# swiatlo.net
KiCad netlist of a schematic drawn in EAGLE
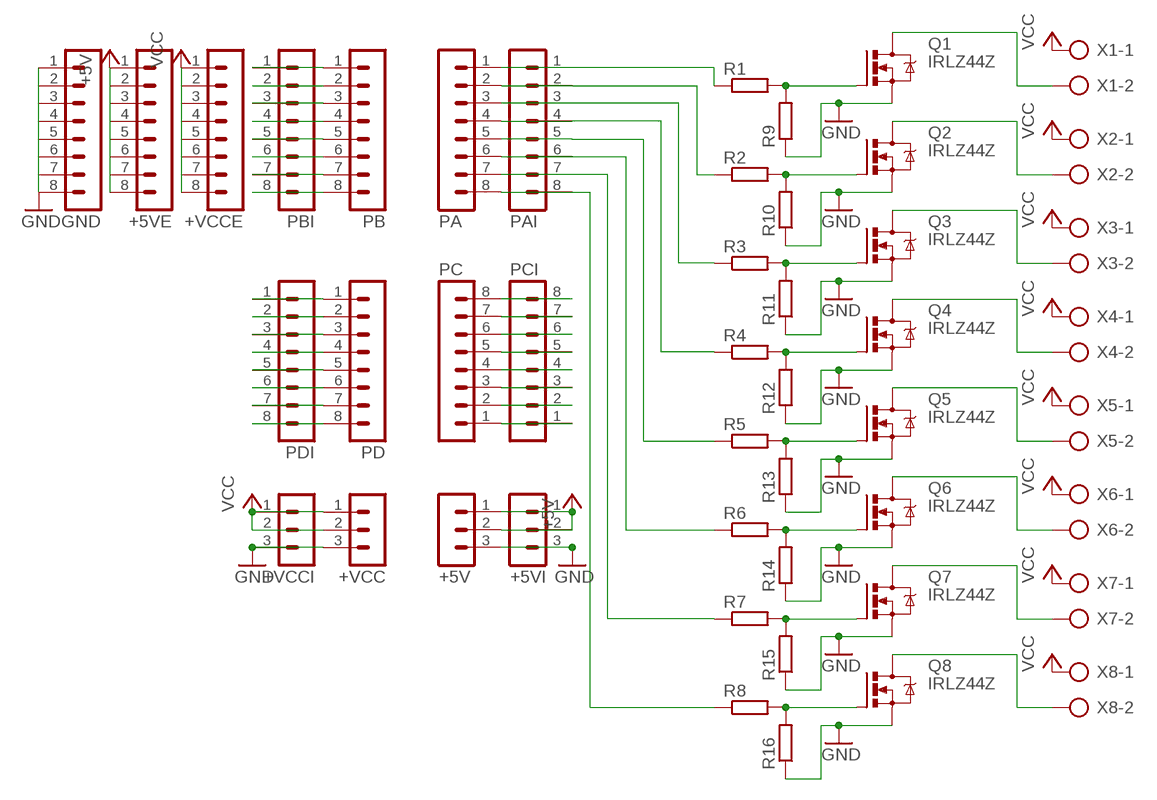
[diagram p0: schematic, sheet 1]

(export (version "E")
  (design (tool "Eeschema 10.0.6"))
  (components
    (comp (ref "+5V")
      (value "MA03-1")
      (footprint "eagle-import:MA03-1")
      (libsource (lib "eagle-import") (part "MA03-1"))
    )
    (comp (ref "+5VE")
      (value "MA08-1")
      (footprint "eagle-import:MA08-1")
      (libsource (lib "eagle-import") (part "MA08-1"))
    )
    (comp (ref "+5VI")
      (value "MA03-1")
      (footprint "eagle-import:MA03-1")
      (libsource (lib "eagle-import") (part "MA03-1"))
    )
    (comp (ref "+VCC")
      (value "MA03-1")
      (footprint "eagle-import:MA03-1")
      (libsource (lib "eagle-import") (part "MA03-1"))
    )
    (comp (ref "+VCCE")
      (value "MA08-1")
      (footprint "eagle-import:MA08-1")
      (libsource (lib "eagle-import") (part "MA08-1"))
    )
    (comp (ref "+VCCI")
      (value "MA03-1")
      (footprint "eagle-import:MA03-1")
      (libsource (lib "eagle-import") (part "MA03-1"))
    )
    (comp (ref "GND")
      (value "MA08-1")
      (footprint "eagle-import:MA08-1")
      (libsource (lib "eagle-import") (part "MA08-1"))
    )
    (comp (ref "PA")
      (value "MA08-1")
      (footprint "eagle-import:MA08-1")
      (libsource (lib "eagle-import") (part "MA08-1"))
    )
    (comp (ref "PAI")
      (value "MA08-1")
      (footprint "eagle-import:MA08-1")
      (libsource (lib "eagle-import") (part "MA08-1"))
    )
    (comp (ref "PB")
      (value "MA08-1")
      (footprint "eagle-import:MA08-1")
      (libsource (lib "eagle-import") (part "MA08-1"))
    )
    (comp (ref "PBI")
      (value "MA08-1")
      (footprint "eagle-import:MA08-1")
      (libsource (lib "eagle-import") (part "MA08-1"))
    )
    (comp (ref "PC")
      (value "MA08-1")
      (footprint "eagle-import:MA08-1")
      (libsource (lib "eagle-import") (part "MA08-1"))
    )
    (comp (ref "PCI")
      (value "MA08-1")
      (footprint "eagle-import:MA08-1")
      (libsource (lib "eagle-import") (part "MA08-1"))
    )
    (comp (ref "PD")
      (value "MA08-1")
      (footprint "eagle-import:MA08-1")
      (libsource (lib "eagle-import") (part "MA08-1"))
    )
    (comp (ref "PDI")
      (value "MA08-1")
      (footprint "eagle-import:MA08-1")
      (libsource (lib "eagle-import") (part "MA08-1"))
    )
    (comp (ref "Q1")
      (value "IRLZ44Z")
      (footprint "eagle-import:TO220BH")
      (libsource (lib "eagle-import") (part "IRLZ44Z"))
    )
    (comp (ref "Q2")
      (value "IRLZ44Z")
      (footprint "eagle-import:TO220BH")
      (libsource (lib "eagle-import") (part "IRLZ44Z"))
    )
    (comp (ref "Q3")
      (value "IRLZ44Z")
      (footprint "eagle-import:TO220BH")
      (libsource (lib "eagle-import") (part "IRLZ44Z"))
    )
    (comp (ref "Q4")
      (value "IRLZ44Z")
      (footprint "eagle-import:TO220BH")
      (libsource (lib "eagle-import") (part "IRLZ44Z"))
    )
    (comp (ref "Q5")
      (value "IRLZ44Z")
      (footprint "eagle-import:TO220BH")
      (libsource (lib "eagle-import") (part "IRLZ44Z"))
    )
    (comp (ref "Q6")
      (value "IRLZ44Z")
      (footprint "eagle-import:TO220BH")
      (libsource (lib "eagle-import") (part "IRLZ44Z"))
    )
    (comp (ref "Q7")
      (value "IRLZ44Z")
      (footprint "eagle-import:TO220BH")
      (libsource (lib "eagle-import") (part "IRLZ44Z"))
    )
    (comp (ref "Q8")
      (value "IRLZ44Z")
      (footprint "eagle-import:TO220BH")
      (libsource (lib "eagle-import") (part "IRLZ44Z"))
    )
    (comp (ref "R1")
      (value "R-EU_0204/7")
      (footprint "eagle-import:0204_7")
      (libsource (lib "eagle-import") (part "R-EU_0204/7"))
    )
    (comp (ref "R2")
      (value "R-EU_0204/7")
      (footprint "eagle-import:0204_7")
      (libsource (lib "eagle-import") (part "R-EU_0204/7"))
    )
    (comp (ref "R3")
      (value "R-EU_0204/7")
      (footprint "eagle-import:0204_7")
      (libsource (lib "eagle-import") (part "R-EU_0204/7"))
    )
    (comp (ref "R4")
      (value "R-EU_0204/7")
      (footprint "eagle-import:0204_7")
      (libsource (lib "eagle-import") (part "R-EU_0204/7"))
    )
    (comp (ref "R5")
      (value "R-EU_0204/7")
      (footprint "eagle-import:0204_7")
      (libsource (lib "eagle-import") (part "R-EU_0204/7"))
    )
    (comp (ref "R6")
      (value "R-EU_0204/7")
      (footprint "eagle-import:0204_7")
      (libsource (lib "eagle-import") (part "R-EU_0204/7"))
    )
    (comp (ref "R7")
      (value "R-EU_0204/7")
      (footprint "eagle-import:0204_7")
      (libsource (lib "eagle-import") (part "R-EU_0204/7"))
    )
    (comp (ref "R8")
      (value "R-EU_0204/7")
      (footprint "eagle-import:0204_7")
      (libsource (lib "eagle-import") (part "R-EU_0204/7"))
    )
    (comp (ref "R9")
      (value "R-EU_0204/7")
      (footprint "eagle-import:0204_7")
      (libsource (lib "eagle-import") (part "R-EU_0204/7"))
    )
    (comp (ref "R10")
      (value "R-EU_0204/7")
      (footprint "eagle-import:0204_7")
      (libsource (lib "eagle-import") (part "R-EU_0204/7"))
    )
    (comp (ref "R11")
      (value "R-EU_0204/7")
      (footprint "eagle-import:0204_7")
      (libsource (lib "eagle-import") (part "R-EU_0204/7"))
    )
    (comp (ref "R12")
      (value "R-EU_0204/7")
      (footprint "eagle-import:0204_7")
      (libsource (lib "eagle-import") (part "R-EU_0204/7"))
    )
    (comp (ref "R13")
      (value "R-EU_0204/7")
      (footprint "eagle-import:0204_7")
      (libsource (lib "eagle-import") (part "R-EU_0204/7"))
    )
    (comp (ref "R14")
      (value "R-EU_0204/7")
      (footprint "eagle-import:0204_7")
      (libsource (lib "eagle-import") (part "R-EU_0204/7"))
    )
    (comp (ref "R15")
      (value "R-EU_0204/7")
      (footprint "eagle-import:0204_7")
      (libsource (lib "eagle-import") (part "R-EU_0204/7"))
    )
    (comp (ref "R16")
      (value "R-EU_0204/7")
      (footprint "eagle-import:0204_7")
      (libsource (lib "eagle-import") (part "R-EU_0204/7"))
    )
    (comp (ref "X1")
      (value "AK300/2")
      (footprint "eagle-import:AK300_2")
      (libsource (lib "eagle-import") (part "AK300/2"))
    )
    (comp (ref "X2")
      (value "AK300/2")
      (footprint "eagle-import:AK300_2")
      (libsource (lib "eagle-import") (part "AK300/2"))
    )
    (comp (ref "X3")
      (value "AK300/2")
      (footprint "eagle-import:AK300_2")
      (libsource (lib "eagle-import") (part "AK300/2"))
    )
    (comp (ref "X4")
      (value "AK300/2")
      (footprint "eagle-import:AK300_2")
      (libsource (lib "eagle-import") (part "AK300/2"))
    )
    (comp (ref "X5")
      (value "AK300/2")
      (footprint "eagle-import:AK300_2")
      (libsource (lib "eagle-import") (part "AK300/2"))
    )
    (comp (ref "X6")
      (value "AK300/2")
      (footprint "eagle-import:AK300_2")
      (libsource (lib "eagle-import") (part "AK300/2"))
    )
    (comp (ref "X7")
      (value "AK300/2")
      (footprint "eagle-import:AK300_2")
      (libsource (lib "eagle-import") (part "AK300/2"))
    )
    (comp (ref "X8")
      (value "AK300/2")
      (footprint "eagle-import:AK300_2")
      (libsource (lib "eagle-import") (part "AK300/2"))
    )
  )
  (nets
    (net (code "1") (name "+5V") (class "Default")
      (node (ref "+5V") (pin "1") (pinfunction "1_1") (pintype "passive"))
      (node (ref "+5V") (pin "2") (pinfunction "2_2") (pintype "passive"))
      (node (ref "+5VE") (pin "1") (pinfunction "1_1") (pintype "passive"))
      (node (ref "+5VE") (pin "2") (pinfunction "2_2") (pintype "passive"))
      (node (ref "+5VE") (pin "3") (pinfunction "3_3") (pintype "passive"))
      (node (ref "+5VE") (pin "4") (pinfunction "4_4") (pintype "passive"))
      (node (ref "+5VE") (pin "5") (pinfunction "5_5") (pintype "passive"))
      (node (ref "+5VE") (pin "6") (pinfunction "6_6") (pintype "passive"))
      (node (ref "+5VE") (pin "7") (pinfunction "7_7") (pintype "passive"))
      (node (ref "+5VE") (pin "8") (pinfunction "8_8") (pintype "passive"))
      (node (ref "+5VI") (pin "1") (pinfunction "1_1") (pintype "passive"))
      (node (ref "+5VI") (pin "2") (pinfunction "2_2") (pintype "passive"))
    )
    (net (code "2") (name "GND") (class "Default")
      (node (ref "+5V") (pin "3") (pinfunction "3_3") (pintype "passive"))
      (node (ref "+5VI") (pin "3") (pinfunction "3_3") (pintype "passive"))
      (node (ref "+VCC") (pin "3") (pinfunction "3_3") (pintype "passive"))
      (node (ref "+VCCI") (pin "3") (pinfunction "3_3") (pintype "passive"))
      (node (ref "GND") (pin "1") (pinfunction "1_1") (pintype "passive"))
      (node (ref "GND") (pin "2") (pinfunction "2_2") (pintype "passive"))
      (node (ref "GND") (pin "3") (pinfunction "3_3") (pintype "passive"))
      (node (ref "GND") (pin "4") (pinfunction "4_4") (pintype "passive"))
      (node (ref "GND") (pin "5") (pinfunction "5_5") (pintype "passive"))
      (node (ref "GND") (pin "6") (pinfunction "6_6") (pintype "passive"))
      (node (ref "GND") (pin "7") (pinfunction "7_7") (pintype "passive"))
      (node (ref "GND") (pin "8") (pinfunction "8_8") (pintype "passive"))
      (node (ref "Q1") (pin "S") (pinfunction "S_S") (pintype "passive"))
      (node (ref "Q2") (pin "S") (pinfunction "S_S") (pintype "passive"))
      (node (ref "Q3") (pin "S") (pinfunction "S_S") (pintype "passive"))
      (node (ref "Q4") (pin "S") (pinfunction "S_S") (pintype "passive"))
      (node (ref "Q5") (pin "S") (pinfunction "S_S") (pintype "passive"))
      (node (ref "Q6") (pin "S") (pinfunction "S_S") (pintype "passive"))
      (node (ref "Q7") (pin "S") (pinfunction "S_S") (pintype "passive"))
      (node (ref "Q8") (pin "S") (pinfunction "S_S") (pintype "passive"))
      (node (ref "R10") (pin "1") (pinfunction "1_1") (pintype "passive"))
      (node (ref "R11") (pin "1") (pinfunction "1_1") (pintype "passive"))
      (node (ref "R12") (pin "1") (pinfunction "1_1") (pintype "passive"))
      (node (ref "R13") (pin "1") (pinfunction "1_1") (pintype "passive"))
      (node (ref "R14") (pin "1") (pinfunction "1_1") (pintype "passive"))
      (node (ref "R15") (pin "1") (pinfunction "1_1") (pintype "passive"))
      (node (ref "R16") (pin "1") (pinfunction "1_1") (pintype "passive"))
      (node (ref "R9") (pin "1") (pinfunction "1_1") (pintype "passive"))
    )
    (net (code "3") (name "Net-(PA-Pad1)") (class "Default")
      (node (ref "PA") (pin "1") (pinfunction "1_1") (pintype "passive"))
      (node (ref "PAI") (pin "1") (pinfunction "1_1") (pintype "passive"))
      (node (ref "R1") (pin "1") (pinfunction "1_1") (pintype "passive"))
    )
    (net (code "4") (name "Net-(PA-Pad2)") (class "Default")
      (node (ref "PA") (pin "2") (pinfunction "2_2") (pintype "passive"))
      (node (ref "PAI") (pin "2") (pinfunction "2_2") (pintype "passive"))
      (node (ref "R2") (pin "1") (pinfunction "1_1") (pintype "passive"))
    )
    (net (code "5") (name "Net-(PA-Pad3)") (class "Default")
      (node (ref "PA") (pin "3") (pinfunction "3_3") (pintype "passive"))
      (node (ref "PAI") (pin "3") (pinfunction "3_3") (pintype "passive"))
      (node (ref "R3") (pin "1") (pinfunction "1_1") (pintype "passive"))
    )
    (net (code "6") (name "Net-(PA-Pad4)") (class "Default")
      (node (ref "PA") (pin "4") (pinfunction "4_4") (pintype "passive"))
      (node (ref "PAI") (pin "4") (pinfunction "4_4") (pintype "passive"))
      (node (ref "R4") (pin "1") (pinfunction "1_1") (pintype "passive"))
    )
    (net (code "7") (name "Net-(PA-Pad5)") (class "Default")
      (node (ref "PA") (pin "5") (pinfunction "5_5") (pintype "passive"))
      (node (ref "PAI") (pin "5") (pinfunction "5_5") (pintype "passive"))
      (node (ref "R5") (pin "1") (pinfunction "1_1") (pintype "passive"))
    )
    (net (code "8") (name "Net-(PA-Pad6)") (class "Default")
      (node (ref "PA") (pin "6") (pinfunction "6_6") (pintype "passive"))
      (node (ref "PAI") (pin "6") (pinfunction "6_6") (pintype "passive"))
      (node (ref "R6") (pin "1") (pinfunction "1_1") (pintype "passive"))
    )
    (net (code "9") (name "Net-(PA-Pad7)") (class "Default")
      (node (ref "PA") (pin "7") (pinfunction "7_7") (pintype "passive"))
      (node (ref "PAI") (pin "7") (pinfunction "7_7") (pintype "passive"))
      (node (ref "R7") (pin "1") (pinfunction "1_1") (pintype "passive"))
    )
    (net (code "10") (name "Net-(PA-Pad8)") (class "Default")
      (node (ref "PA") (pin "8") (pinfunction "8_8") (pintype "passive"))
      (node (ref "PAI") (pin "8") (pinfunction "8_8") (pintype "passive"))
      (node (ref "R8") (pin "1") (pinfunction "1_1") (pintype "passive"))
    )
    (net (code "11") (name "Net-(PB-Pad1)") (class "Default")
      (node (ref "PB") (pin "1") (pinfunction "1_1") (pintype "passive"))
      (node (ref "PBI") (pin "1") (pinfunction "1_1") (pintype "passive"))
    )
    (net (code "12") (name "Net-(PB-Pad2)") (class "Default")
      (node (ref "PB") (pin "2") (pinfunction "2_2") (pintype "passive"))
      (node (ref "PBI") (pin "2") (pinfunction "2_2") (pintype "passive"))
    )
    (net (code "13") (name "Net-(PB-Pad3)") (class "Default")
      (node (ref "PB") (pin "3") (pinfunction "3_3") (pintype "passive"))
      (node (ref "PBI") (pin "3") (pinfunction "3_3") (pintype "passive"))
    )
    (net (code "14") (name "Net-(PB-Pad4)") (class "Default")
      (node (ref "PB") (pin "4") (pinfunction "4_4") (pintype "passive"))
      (node (ref "PBI") (pin "4") (pinfunction "4_4") (pintype "passive"))
    )
    (net (code "15") (name "Net-(PB-Pad5)") (class "Default")
      (node (ref "PB") (pin "5") (pinfunction "5_5") (pintype "passive"))
      (node (ref "PBI") (pin "5") (pinfunction "5_5") (pintype "passive"))
    )
    (net (code "16") (name "Net-(PB-Pad6)") (class "Default")
      (node (ref "PB") (pin "6") (pinfunction "6_6") (pintype "passive"))
      (node (ref "PBI") (pin "6") (pinfunction "6_6") (pintype "passive"))
    )
    (net (code "17") (name "Net-(PB-Pad7)") (class "Default")
      (node (ref "PB") (pin "7") (pinfunction "7_7") (pintype "passive"))
      (node (ref "PBI") (pin "7") (pinfunction "7_7") (pintype "passive"))
    )
    (net (code "18") (name "Net-(PB-Pad8)") (class "Default")
      (node (ref "PB") (pin "8") (pinfunction "8_8") (pintype "passive"))
      (node (ref "PBI") (pin "8") (pinfunction "8_8") (pintype "passive"))
    )
    (net (code "19") (name "Net-(PC-Pad1)") (class "Default")
      (node (ref "PC") (pin "1") (pinfunction "1_1") (pintype "passive"))
      (node (ref "PCI") (pin "1") (pinfunction "1_1") (pintype "passive"))
    )
    (net (code "20") (name "Net-(PC-Pad2)") (class "Default")
      (node (ref "PC") (pin "2") (pinfunction "2_2") (pintype "passive"))
      (node (ref "PCI") (pin "2") (pinfunction "2_2") (pintype "passive"))
    )
    (net (code "21") (name "Net-(PC-Pad3)") (class "Default")
      (node (ref "PC") (pin "3") (pinfunction "3_3") (pintype "passive"))
      (node (ref "PCI") (pin "3") (pinfunction "3_3") (pintype "passive"))
    )
    (net (code "22") (name "Net-(PC-Pad4)") (class "Default")
      (node (ref "PC") (pin "4") (pinfunction "4_4") (pintype "passive"))
      (node (ref "PCI") (pin "4") (pinfunction "4_4") (pintype "passive"))
    )
    (net (code "23") (name "Net-(PC-Pad5)") (class "Default")
      (node (ref "PC") (pin "5") (pinfunction "5_5") (pintype "passive"))
      (node (ref "PCI") (pin "5") (pinfunction "5_5") (pintype "passive"))
    )
    (net (code "24") (name "Net-(PC-Pad6)") (class "Default")
      (node (ref "PC") (pin "6") (pinfunction "6_6") (pintype "passive"))
      (node (ref "PCI") (pin "6") (pinfunction "6_6") (pintype "passive"))
    )
    (net (code "25") (name "Net-(PC-Pad7)") (class "Default")
      (node (ref "PC") (pin "7") (pinfunction "7_7") (pintype "passive"))
      (node (ref "PCI") (pin "7") (pinfunction "7_7") (pintype "passive"))
    )
    (net (code "26") (name "Net-(PC-Pad8)") (class "Default")
      (node (ref "PC") (pin "8") (pinfunction "8_8") (pintype "passive"))
      (node (ref "PCI") (pin "8") (pinfunction "8_8") (pintype "passive"))
    )
    (net (code "27") (name "Net-(PD-Pad1)") (class "Default")
      (node (ref "PD") (pin "1") (pinfunction "1_1") (pintype "passive"))
      (node (ref "PDI") (pin "1") (pinfunction "1_1") (pintype "passive"))
    )
    (net (code "28") (name "Net-(PD-Pad2)") (class "Default")
      (node (ref "PD") (pin "2") (pinfunction "2_2") (pintype "passive"))
      (node (ref "PDI") (pin "2") (pinfunction "2_2") (pintype "passive"))
    )
    (net (code "29") (name "Net-(PD-Pad3)") (class "Default")
      (node (ref "PD") (pin "3") (pinfunction "3_3") (pintype "passive"))
      (node (ref "PDI") (pin "3") (pinfunction "3_3") (pintype "passive"))
    )
    (net (code "30") (name "Net-(PD-Pad4)") (class "Default")
      (node (ref "PD") (pin "4") (pinfunction "4_4") (pintype "passive"))
      (node (ref "PDI") (pin "4") (pinfunction "4_4") (pintype "passive"))
    )
    (net (code "31") (name "Net-(PD-Pad5)") (class "Default")
      (node (ref "PD") (pin "5") (pinfunction "5_5") (pintype "passive"))
      (node (ref "PDI") (pin "5") (pinfunction "5_5") (pintype "passive"))
    )
    (net (code "32") (name "Net-(PD-Pad6)") (class "Default")
      (node (ref "PD") (pin "6") (pinfunction "6_6") (pintype "passive"))
      (node (ref "PDI") (pin "6") (pinfunction "6_6") (pintype "passive"))
    )
    (net (code "33") (name "Net-(PD-Pad7)") (class "Default")
      (node (ref "PD") (pin "7") (pinfunction "7_7") (pintype "passive"))
      (node (ref "PDI") (pin "7") (pinfunction "7_7") (pintype "passive"))
    )
    (net (code "34") (name "Net-(PD-Pad8)") (class "Default")
      (node (ref "PD") (pin "8") (pinfunction "8_8") (pintype "passive"))
      (node (ref "PDI") (pin "8") (pinfunction "8_8") (pintype "passive"))
    )
    (net (code "35") (name "Net-(Q1-PadG)") (class "Default")
      (node (ref "Q1") (pin "G") (pinfunction "G_G") (pintype "passive"))
      (node (ref "R1") (pin "2") (pinfunction "2_2") (pintype "passive"))
      (node (ref "R9") (pin "2") (pinfunction "2_2") (pintype "passive"))
    )
    (net (code "36") (name "Net-(Q2-PadG)") (class "Default")
      (node (ref "Q2") (pin "G") (pinfunction "G_G") (pintype "passive"))
      (node (ref "R10") (pin "2") (pinfunction "2_2") (pintype "passive"))
      (node (ref "R2") (pin "2") (pinfunction "2_2") (pintype "passive"))
    )
    (net (code "37") (name "Net-(Q3-PadG)") (class "Default")
      (node (ref "Q3") (pin "G") (pinfunction "G_G") (pintype "passive"))
      (node (ref "R11") (pin "2") (pinfunction "2_2") (pintype "passive"))
      (node (ref "R3") (pin "2") (pinfunction "2_2") (pintype "passive"))
    )
    (net (code "38") (name "Net-(Q4-PadG)") (class "Default")
      (node (ref "Q4") (pin "G") (pinfunction "G_G") (pintype "passive"))
      (node (ref "R12") (pin "2") (pinfunction "2_2") (pintype "passive"))
      (node (ref "R4") (pin "2") (pinfunction "2_2") (pintype "passive"))
    )
    (net (code "39") (name "Net-(Q5-PadG)") (class "Default")
      (node (ref "Q5") (pin "G") (pinfunction "G_G") (pintype "passive"))
      (node (ref "R13") (pin "2") (pinfunction "2_2") (pintype "passive"))
      (node (ref "R5") (pin "2") (pinfunction "2_2") (pintype "passive"))
    )
    (net (code "40") (name "Net-(Q6-PadG)") (class "Default")
      (node (ref "Q6") (pin "G") (pinfunction "G_G") (pintype "passive"))
      (node (ref "R14") (pin "2") (pinfunction "2_2") (pintype "passive"))
      (node (ref "R6") (pin "2") (pinfunction "2_2") (pintype "passive"))
    )
    (net (code "41") (name "Net-(Q7-PadG)") (class "Default")
      (node (ref "Q7") (pin "G") (pinfunction "G_G") (pintype "passive"))
      (node (ref "R15") (pin "2") (pinfunction "2_2") (pintype "passive"))
      (node (ref "R7") (pin "2") (pinfunction "2_2") (pintype "passive"))
    )
    (net (code "42") (name "Net-(Q8-PadG)") (class "Default")
      (node (ref "Q8") (pin "G") (pinfunction "G_G") (pintype "passive"))
      (node (ref "R16") (pin "2") (pinfunction "2_2") (pintype "passive"))
      (node (ref "R8") (pin "2") (pinfunction "2_2") (pintype "passive"))
    )
    (net (code "43") (name "Net-(X1B-KL)") (class "Default")
      (node (ref "Q1") (pin "D") (pinfunction "D_D") (pintype "passive"))
      (node (ref "X1") (pin "2") (pinfunction "KL_2") (pintype "passive"))
    )
    (net (code "44") (name "Net-(X2B-KL)") (class "Default")
      (node (ref "Q2") (pin "D") (pinfunction "D_D") (pintype "passive"))
      (node (ref "X2") (pin "2") (pinfunction "KL_2") (pintype "passive"))
    )
    (net (code "45") (name "Net-(X3B-KL)") (class "Default")
      (node (ref "Q3") (pin "D") (pinfunction "D_D") (pintype "passive"))
      (node (ref "X3") (pin "2") (pinfunction "KL_2") (pintype "passive"))
    )
    (net (code "46") (name "Net-(X4B-KL)") (class "Default")
      (node (ref "Q4") (pin "D") (pinfunction "D_D") (pintype "passive"))
      (node (ref "X4") (pin "2") (pinfunction "KL_2") (pintype "passive"))
    )
    (net (code "47") (name "Net-(X5B-KL)") (class "Default")
      (node (ref "Q5") (pin "D") (pinfunction "D_D") (pintype "passive"))
      (node (ref "X5") (pin "2") (pinfunction "KL_2") (pintype "passive"))
    )
    (net (code "48") (name "Net-(X6B-KL)") (class "Default")
      (node (ref "Q6") (pin "D") (pinfunction "D_D") (pintype "passive"))
      (node (ref "X6") (pin "2") (pinfunction "KL_2") (pintype "passive"))
    )
    (net (code "49") (name "Net-(X7B-KL)") (class "Default")
      (node (ref "Q7") (pin "D") (pinfunction "D_D") (pintype "passive"))
      (node (ref "X7") (pin "2") (pinfunction "KL_2") (pintype "passive"))
    )
    (net (code "50") (name "Net-(X8B-KL)") (class "Default")
      (node (ref "Q8") (pin "D") (pinfunction "D_D") (pintype "passive"))
      (node (ref "X8") (pin "2") (pinfunction "KL_2") (pintype "passive"))
    )
    (net (code "51") (name "VCC") (class "Default")
      (node (ref "+VCC") (pin "1") (pinfunction "1_1") (pintype "passive"))
      (node (ref "+VCC") (pin "2") (pinfunction "2_2") (pintype "passive"))
      (node (ref "+VCCE") (pin "1") (pinfunction "1_1") (pintype "passive"))
      (node (ref "+VCCE") (pin "2") (pinfunction "2_2") (pintype "passive"))
      (node (ref "+VCCE") (pin "3") (pinfunction "3_3") (pintype "passive"))
      (node (ref "+VCCE") (pin "4") (pinfunction "4_4") (pintype "passive"))
      (node (ref "+VCCE") (pin "5") (pinfunction "5_5") (pintype "passive"))
      (node (ref "+VCCE") (pin "6") (pinfunction "6_6") (pintype "passive"))
      (node (ref "+VCCE") (pin "7") (pinfunction "7_7") (pintype "passive"))
      (node (ref "+VCCE") (pin "8") (pinfunction "8_8") (pintype "passive"))
      (node (ref "+VCCI") (pin "1") (pinfunction "1_1") (pintype "passive"))
      (node (ref "+VCCI") (pin "2") (pinfunction "2_2") (pintype "passive"))
      (node (ref "X1") (pin "1") (pinfunction "KL_1") (pintype "passive"))
      (node (ref "X2") (pin "1") (pinfunction "KL_1") (pintype "passive"))
      (node (ref "X3") (pin "1") (pinfunction "KL_1") (pintype "passive"))
      (node (ref "X4") (pin "1") (pinfunction "KL_1") (pintype "passive"))
      (node (ref "X5") (pin "1") (pinfunction "KL_1") (pintype "passive"))
      (node (ref "X6") (pin "1") (pinfunction "KL_1") (pintype "passive"))
      (node (ref "X7") (pin "1") (pinfunction "KL_1") (pintype "passive"))
      (node (ref "X8") (pin "1") (pinfunction "KL_1") (pintype "passive"))
    )
  )
)
